# MCU.net
KiCad netlist of a schematic drawn in Altium Designer
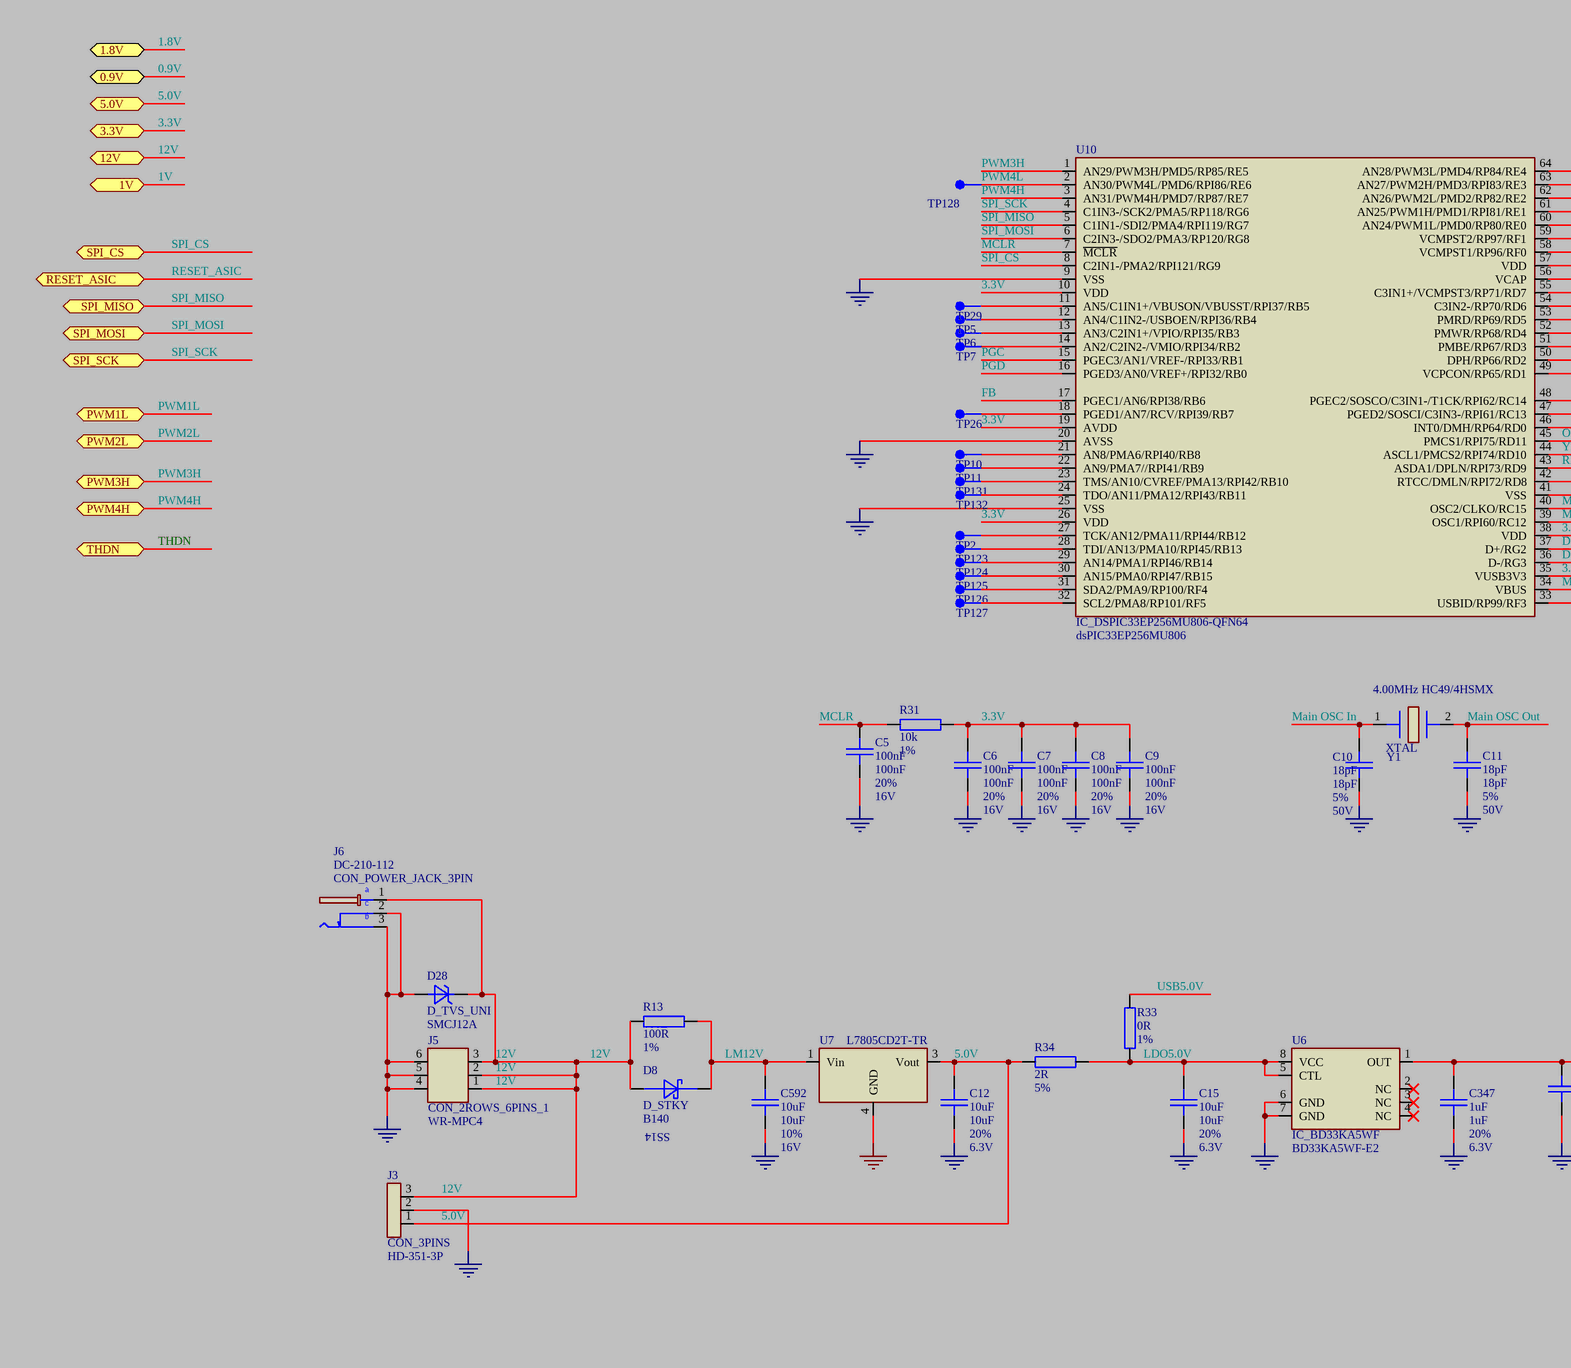
[diagram p0: MCU.SchDoc, left]
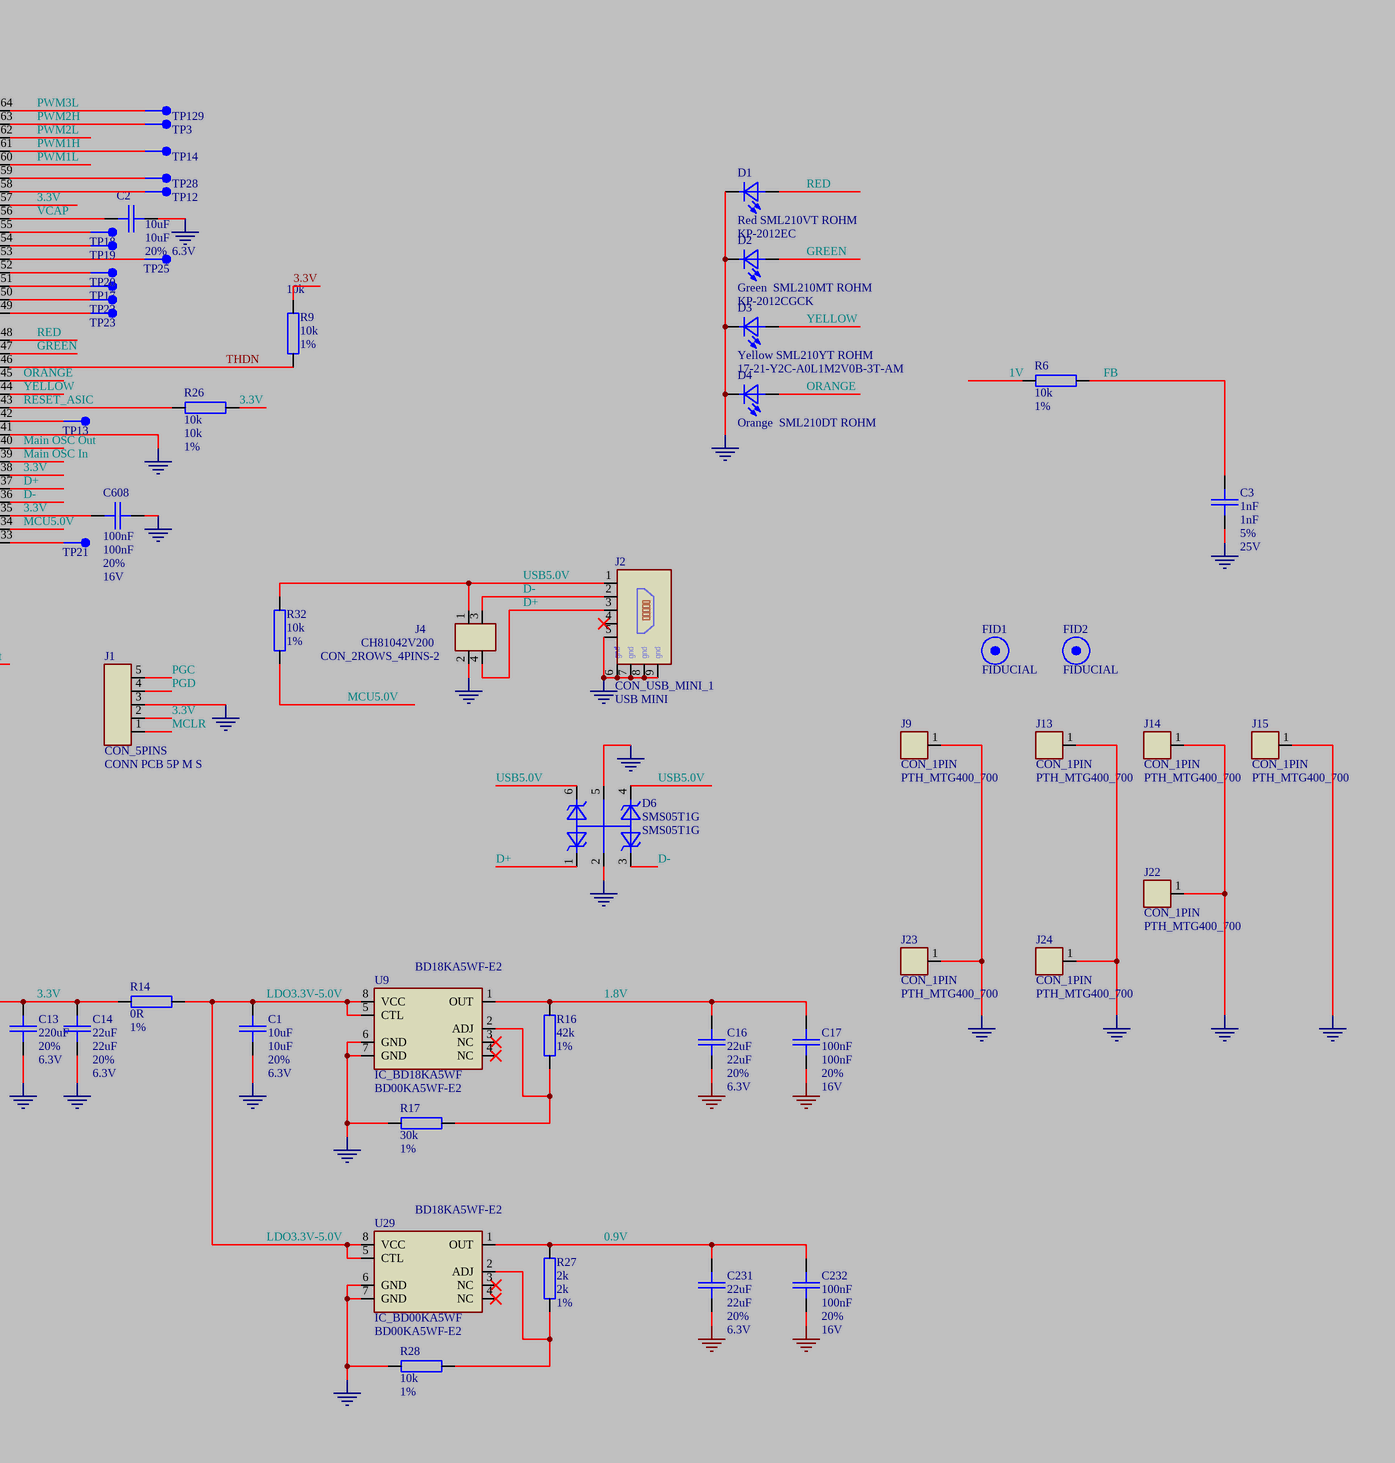
[diagram p1: MCU.SchDoc, right]

(export (version "E")
  (design (tool "Eeschema 10.0.6"))
  (components
    (comp (ref "C1")
      (value "10uF")
      (footprint "SMD_0603_CAPC1608X95N")
      (fields
        (field (name "DB_PART_NUMBER") "CAP000043646")
        (field (name "DB_VALUE") "10uF")
        (field (name "DB_TOLERANCE") "20%")
        (field (name "DB_VOLTAGE") "6.3V")
        (field (name "DB_MANUFACTURER_PART") "KEMET    C0603C106M9PAC")
        (field (name "DB_APPROVED_BY") "ISHIDDEN=T")
      )
      (libsource (lib "Database_Libs1") (part "C"))
    )
    (comp (ref "C2")
      (value "10uF")
      (footprint "SMD_0603_CAPC1608X95N")
      (fields
        (field (name "DB_PART_NUMBER") "CAP000043646")
        (field (name "DB_VALUE") "10uF")
        (field (name "DB_TOLERANCE") "20%")
        (field (name "DB_VOLTAGE") "6.3V")
        (field (name "DB_MANUFACTURER_PART") "KEMET    C0603C106M9PAC")
        (field (name "DB_APPROVED_BY") "ISHIDDEN=T")
      )
      (libsource (lib "Database_Libs1") (part "C"))
    )
    (comp (ref "C3")
      (value "1nF")
      (footprint "SMD_0603_CAPC1608X95N")
      (fields
        (field (name "DB_PART_NUMBER") "CAP000024113")
        (field (name "DB_VALUE") "1nF")
        (field (name "DB_TOLERANCE") "5%")
        (field (name "DB_VOLTAGE") "25V")
        (field (name "DB_MANUFACTURER_PART") "KEMET    C0603C102J3RAC")
        (field (name "DB_APPROVED_BY") "ISHIDDEN=T")
      )
      (libsource (lib "Database_Libs1") (part "C"))
    )
    (comp (ref "C5")
      (value "100nF")
      (footprint "SMD_0603_CAPC1608X95N")
      (fields
        (field (name "DB_PART_NUMBER") "CAP000027236")
        (field (name "DB_VALUE") "100nF")
        (field (name "DB_TOLERANCE") "20%")
        (field (name "DB_VOLTAGE") "16V")
        (field (name "DB_MANUFACTURER_PART") "KEMET    C0603C104M4RAC")
        (field (name "DB_APPROVED_BY") "ISHIDDEN=T")
      )
      (libsource (lib "Database_Libs1") (part "C"))
    )
    (comp (ref "C6")
      (value "100nF")
      (footprint "SMD_0603_CAPC1608X95N")
      (fields
        (field (name "DB_PART_NUMBER") "CAP000027236")
        (field (name "DB_VALUE") "100nF")
        (field (name "DB_TOLERANCE") "20%")
        (field (name "DB_VOLTAGE") "16V")
        (field (name "DB_MANUFACTURER_PART") "KEMET    C0603C104M4RAC")
        (field (name "DB_APPROVED_BY") "ISHIDDEN=T")
      )
      (libsource (lib "Database_Libs1") (part "C"))
    )
    (comp (ref "C7")
      (value "100nF")
      (footprint "SMD_0603_CAPC1608X95N")
      (fields
        (field (name "DB_PART_NUMBER") "CAP000027236")
        (field (name "DB_VALUE") "100nF")
        (field (name "DB_TOLERANCE") "20%")
        (field (name "DB_VOLTAGE") "16V")
        (field (name "DB_MANUFACTURER_PART") "KEMET    C0603C104M4RAC")
        (field (name "DB_APPROVED_BY") "ISHIDDEN=T")
      )
      (libsource (lib "Database_Libs1") (part "C"))
    )
    (comp (ref "C8")
      (value "100nF")
      (footprint "SMD_0603_CAPC1608X95N")
      (fields
        (field (name "DB_PART_NUMBER") "CAP000027236")
        (field (name "DB_VALUE") "100nF")
        (field (name "DB_TOLERANCE") "20%")
        (field (name "DB_VOLTAGE") "16V")
        (field (name "DB_MANUFACTURER_PART") "KEMET    C0603C104M4RAC")
        (field (name "DB_APPROVED_BY") "ISHIDDEN=T")
      )
      (libsource (lib "Database_Libs1") (part "C"))
    )
    (comp (ref "C9")
      (value "100nF")
      (footprint "SMD_0603_CAPC1608X95N")
      (fields
        (field (name "DB_PART_NUMBER") "CAP000027236")
        (field (name "DB_VALUE") "100nF")
        (field (name "DB_TOLERANCE") "20%")
        (field (name "DB_VOLTAGE") "16V")
        (field (name "DB_MANUFACTURER_PART") "KEMET    C0603C104M4RAC")
        (field (name "DB_APPROVED_BY") "ISHIDDEN=T")
      )
      (libsource (lib "Database_Libs1") (part "C"))
    )
    (comp (ref "C10")
      (value "18pF")
      (footprint "SMD_0603_CAPC1608X95N")
      (fields
        (field (name "DB_PART_NUMBER") "CAP000031922")
        (field (name "DB_VALUE") "18pF")
        (field (name "DB_TOLERANCE") "5%")
        (field (name "DB_VOLTAGE") "50V")
        (field (name "DB_MANUFACTURER_PART") "KEMET    C0603C180J5GAC")
        (field (name "DB_APPROVED_BY") "ISHIDDEN=T")
      )
      (libsource (lib "Database_Libs1") (part "C"))
    )
    (comp (ref "C11")
      (value "18pF")
      (footprint "SMD_0603_CAPC1608X95N")
      (fields
        (field (name "DB_PART_NUMBER") "CAP000031922")
        (field (name "DB_VALUE") "18pF")
        (field (name "DB_TOLERANCE") "5%")
        (field (name "DB_VOLTAGE") "50V")
        (field (name "DB_MANUFACTURER_PART") "KEMET    C0603C180J5GAC")
        (field (name "DB_APPROVED_BY") "ISHIDDEN=T")
      )
      (libsource (lib "Database_Libs1") (part "C"))
    )
    (comp (ref "C12")
      (value "10uF")
      (footprint "SMD_0603_CAPC1608X95N")
      (fields
        (field (name "DB_PART_NUMBER") "CAP000043646")
        (field (name "DB_VALUE") "10uF")
        (field (name "DB_TOLERANCE") "20%")
        (field (name "DB_VOLTAGE") "6.3V")
        (field (name "DB_MANUFACTURER_PART") "KEMET    C0603C106M9PAC")
        (field (name "DB_APPROVED_BY") "ISHIDDEN=T")
      )
      (libsource (lib "Database_Libs1") (part "C"))
    )
    (comp (ref "C13")
      (value "220uF")
      (footprint "SMD_1210_CAPC3225X279N")
      (fields
        (field (name "DB_PART_NUMBER") "CAP000047355")
        (field (name "DB_VALUE") "220uF")
        (field (name "DB_TOLERANCE") "20%")
        (field (name "DB_VOLTAGE") "6.3V")
        (field (name "DB_MANUFACTURER_PART") "SAMSUNG    CL32A227MQVNNNE")
        (field (name "DB_APPROVED_BY") "VSN")
      )
      (libsource (lib "Database_Libs1") (part "C"))
    )
    (comp (ref "C14")
      (value "22uF")
      (footprint "SMD_0805_CAPC2012X145N")
      (fields
        (field (name "DB_PART_NUMBER") "CAP000043686")
        (field (name "DB_VALUE") "22uF")
        (field (name "DB_TOLERANCE") "20%")
        (field (name "DB_VOLTAGE") "6.3V")
        (field (name "DB_MANUFACTURER_PART") "KEMET    C0805C226M9PAC")
        (field (name "DB_APPROVED_BY") "ISHIDDEN=T")
      )
      (libsource (lib "Database_Libs1") (part "C"))
    )
    (comp (ref "C15")
      (value "10uF")
      (footprint "SMD_0603_CAPC1608X95N")
      (fields
        (field (name "DB_PART_NUMBER") "CAP000043646")
        (field (name "DB_VALUE") "10uF")
        (field (name "DB_TOLERANCE") "20%")
        (field (name "DB_VOLTAGE") "6.3V")
        (field (name "DB_MANUFACTURER_PART") "KEMET    C0603C106M9PAC")
        (field (name "DB_APPROVED_BY") "ISHIDDEN=T")
      )
      (libsource (lib "Database_Libs1") (part "C"))
    )
    (comp (ref "C16")
      (value "22uF")
      (footprint "SMD_0805_CAPC2012X145N")
      (fields
        (field (name "DB_PART_NUMBER") "CAP000043686")
        (field (name "DB_VALUE") "22uF")
        (field (name "DB_TOLERANCE") "20%")
        (field (name "DB_VOLTAGE") "6.3V")
        (field (name "DB_MANUFACTURER_PART") "KEMET    C0805C226M9PAC")
        (field (name "DB_APPROVED_BY") "ISHIDDEN=T")
      )
      (libsource (lib "Database_Libs1") (part "C"))
    )
    (comp (ref "C17")
      (value "100nF")
      (footprint "SMD_0603_CAPC1608X95N")
      (fields
        (field (name "DB_PART_NUMBER") "CAP000027236")
        (field (name "DB_VALUE") "100nF")
        (field (name "DB_TOLERANCE") "20%")
        (field (name "DB_VOLTAGE") "16V")
        (field (name "DB_MANUFACTURER_PART") "KEMET    C0603C104M4RAC")
        (field (name "DB_APPROVED_BY") "ISHIDDEN=T")
      )
      (libsource (lib "Database_Libs1") (part "C"))
    )
    (comp (ref "C231")
      (value "22uF")
      (footprint "SMD_0805_CAPC2012X145N")
      (fields
        (field (name "DB_PART_NUMBER") "CAP000043686")
        (field (name "DB_VALUE") "22uF")
        (field (name "DB_TOLERANCE") "20%")
        (field (name "DB_VOLTAGE") "6.3V")
        (field (name "DB_MANUFACTURER_PART") "KEMET    C0805C226M9PAC")
        (field (name "DB_APPROVED_BY") "ISHIDDEN=T")
      )
      (libsource (lib "Database_Libs1") (part "C"))
    )
    (comp (ref "C232")
      (value "100nF")
      (footprint "SMD_0603_CAPC1608X95N")
      (fields
        (field (name "DB_PART_NUMBER") "CAP000027236")
        (field (name "DB_VALUE") "100nF")
        (field (name "DB_TOLERANCE") "20%")
        (field (name "DB_VOLTAGE") "16V")
        (field (name "DB_MANUFACTURER_PART") "KEMET    C0603C104M4RAC")
        (field (name "DB_APPROVED_BY") "ISHIDDEN=T")
      )
      (libsource (lib "Database_Libs1") (part "C"))
    )
    (comp (ref "C347")
      (value "1uF")
      (footprint "SMD_0603_CAPC1608X95N")
      (fields
        (field (name "DB_PART_NUMBER") "CAP000043344")
        (field (name "DB_VALUE") "1uF")
        (field (name "DB_TOLERANCE") "20%")
        (field (name "DB_VOLTAGE") "6.3V")
        (field (name "DB_MANUFACTURER_PART") "KEMET    C0603C105M9PAC")
        (field (name "DB_APPROVED_BY") "ISHIDDEN=T")
      )
      (libsource (lib "Database_Libs1") (part "C"))
    )
    (comp (ref "C592")
      (value "10uF")
      (footprint "SMD_0805_CAPC2012X145N")
      (fields
        (field (name "DB_PART_NUMBER") "CAP000043636")
        (field (name "DB_VALUE") "10uF")
        (field (name "DB_TOLERANCE") "10%")
        (field (name "DB_VOLTAGE") "16V")
        (field (name "DB_MANUFACTURER_PART") "KEMET    C0805C106K4PAC")
        (field (name "DB_APPROVED_BY") "ISHIDDEN=T")
      )
      (libsource (lib "Database_Libs1") (part "C"))
    )
    (comp (ref "C608")
      (value "100nF")
      (footprint "SMD_0603_CAPC1608X95N")
      (fields
        (field (name "DB_PART_NUMBER") "CAP000027236")
        (field (name "DB_VALUE") "100nF")
        (field (name "DB_TOLERANCE") "20%")
        (field (name "DB_VOLTAGE") "16V")
        (field (name "DB_MANUFACTURER_PART") "KEMET    C0603C104M4RAC")
        (field (name "DB_APPROVED_BY") "ISHIDDEN=T")
      )
      (libsource (lib "Database_Libs1") (part "C"))
    )
    (comp (ref "D1")
      (value "Red SML210VT ROHM")
      (footprint "SMD_0805_LED2012X100N")
      (fields
        (field (name "DB_PART_NUMBER") "OPT000000095")
        (field (name "DB_MANUFACTURER_PART") "KINGBRIGHT       KP-2012EC")
        (field (name "DB_VALUE") "KP-2012EC")
        (field (name "DB_APPROVED_BY") "VSN")
      )
      (libsource (lib "Database_Libs1") (part "LED"))
    )
    (comp (ref "D2")
      (value "Green  SML210MT ROHM")
      (footprint "SMD_0805_LED2012X100N")
      (fields
        (field (name "DB_PART_NUMBER") "OPT000000096")
        (field (name "DB_MANUFACTURER_PART") "KINGBRIGHT       KP-2012CGCK")
        (field (name "DB_VALUE") "KP-2012CGCK")
        (field (name "DB_APPROVED_BY") "VSN")
      )
      (libsource (lib "Database_Libs1") (part "LED"))
    )
    (comp (ref "D3")
      (value "Yellow SML210YT ROHM")
      (footprint "SMD_0805_LED2012X100N")
      (fields
        (field (name "DB_PART_NUMBER") "OPT000000092")
        (field (name "DB_MANUFACTURER_PART") "EVERLIGHT       17-21-Y2C-A0L1M2V0B-3T-AM")
        (field (name "DB_VALUE") "17-21-Y2C-A0L1M2V0B-3T-AM")
        (field (name "DB_APPROVED_BY") "VSN")
      )
      (libsource (lib "Database_Libs1") (part "LED"))
    )
    (comp (ref "D4")
      (value "Orange  SML210DT ROHM")
      (footprint "SMD_0805_LED2012X100N")
      (fields
        (field (name "DB_PART_NUMBER") "OPT000000096")
        (field (name "DB_MANUFACTURER_PART") "KINGBRIGHT       KP-2012CGCK")
        (field (name "DB_APPROVED_BY") "VSN")
      )
      (libsource (lib "altium-import") (part "root_0_LED_Orange_"))
    )
    (comp (ref "D6")
      (value "SMS05T1G")
      (footprint "SMD_SOT457_SOT95P275X110-6N")
      (fields
        (field (name "DB_PART_NUMBER") "DDE000002846")
        (field (name "DB_VALUE") "SMS05T1G")
        (field (name "DB_MANUFACTURER_PART") "ON SEMICONDUCTOR        SMS05T1G")
        (field (name "DB_APPROVED_BY") "VSN")
      )
      (libsource (lib "Database_Libs1") (part "D_TVS_QUAD_C1A2C3C4A5C6"))
    )
    (comp (ref "D8")
      (value "D_STKY")
      (footprint "SMD_DO214AC_SMA")
      (fields
        (field (name "DB_PART_NUMBER") "DDE000000580")
        (field (name "DB_VALUE") "B140")
        (field (name "DB_MANUFACTURER_PART") "Diodes        B140")
        (field (name "DB_APPROVED_BY") "ISHIDDEN=T")
      )
      (libsource (lib "Database_Libs1") (part "D_STKY"))
    )
    (comp (ref "D28")
      (value "D_TVS_UNI")
      (footprint "SMD_DO214AC_SMC")
      (fields
        (field (name "DB_PART_NUMBER") "DDE000001725")
        (field (name "DB_VALUE") "SMCJ12A")
        (field (name "DB_MANUFACTURER_PART") "Diodes        SMCJ12A")
        (field (name "DB_APPROVED_BY") "ISHIDDEN=T")
      )
      (libsource (lib "Database_Libs1") (part "D_TVS_UNI"))
    )
    (comp (ref "FID1")
      (value "FIDUCIAL")
      (footprint "FID100X200")
      (fields
        (field (name "DB_PART_NUMBER") "FID000000001")
        (field (name "DB_MANUFACTURER_PART") "ISHIDDEN=T")
        (field (name "DB_APPROVED_BY") "ISHIDDEN=T")
      )
      (libsource (lib "Database_Libs1") (part "FIDUCIAL"))
    )
    (comp (ref "FID2")
      (value "FIDUCIAL")
      (footprint "FID100X200")
      (fields
        (field (name "DB_PART_NUMBER") "FID000000001")
        (field (name "DB_MANUFACTURER_PART") "ISHIDDEN=T")
        (field (name "DB_APPROVED_BY") "ISHIDDEN=T")
      )
      (libsource (lib "Database_Libs1") (part "FIDUCIAL"))
    )
    (comp (ref "J1")
      (value "CON_5PINS")
      (footprint "PTH_HDRV05W64P254_1X05")
      (fields
        (field (name "DB_PART_NUMBER") "CON000000006")
        (field (name "DB_VALUE") "CONN PCB 5P M S")
        (field (name "DB_MANUFACTURER_PART") "W+P        143-12-005-00")
        (field (name "DB_APPROVED_BY") "VSN")
      )
      (libsource (lib "Database_Libs1") (part "CON_5PINS"))
    )
    (comp (ref "J2")
      (value "CON_USB_MINI_1")
      (footprint "SMD_CON-CVILUX-CU04-SCM15B0")
      (fields
        (field (name "DB_PART_NUMBER") "CON000000048")
        (field (name "DB_VALUE") "USB MINI")
        (field (name "DB_MANUFACTURER_PART") "CVILUX       CU04-SCM15B0-R0-LF")
        (field (name "DB_APPROVED_BY") "VSN")
      )
      (libsource (lib "Database_Libs1") (part "CON_USB_MINI_1"))
    )
    (comp (ref "J3")
      (value "CON_3PINS")
      (footprint "PTH_CON_HD-351-3P")
      (fields
        (field (name "DB_PART_NUMBER") "CON000000272")
        (field (name "DB_VALUE") "HD-351-3P")
        (field (name "DB_MANUFACTURER_PART") "HOW DER      HD-351-3P")
        (field (name "DB_APPROVED_BY") "VSN")
      )
      (libsource (lib "Database_Libs1") (part "CON_3PINS"))
    )
    (comp (ref "J4")
      (value "CON_2ROWS_4PINS-2")
      (footprint "PTH_HDRV40W6240P254_2X02_M")
      (fields
        (field (name "DB_PART_NUMBER") "CON000000298")
        (field (name "DB_VALUE") "CH81042V200")
        (field (name "DB_MANUFACTURER_PART") "CVILUX        CH81042V200")
        (field (name "DB_APPROVED_BY") "VSN")
      )
      (libsource (lib "Database_Libs1") (part "CON_2ROWS_4PINS-2"))
    )
    (comp (ref "J5")
      (value "CON_2ROWS_6PINS_1")
      (footprint "PTH_CON_WR-MRC4-6P")
      (fields
        (field (name "DB_PART_NUMBER") "CON000000271")
        (field (name "DB_VALUE") "WR-MPC4")
        (field (name "DB_MANUFACTURER_PART") "WE         649 006 295 22")
        (field (name "DB_APPROVED_BY") "VSN")
      )
      (libsource (lib "Database_Libs1") (part "CON_2ROWS_6PINS_1"))
    )
    (comp (ref "J6")
      (value "CON_POWER_JACK_3PIN")
      (footprint "PTH_DC-POWER-JACK_210-112")
      (fields
        (field (name "DB_PART_NUMBER") "CON000000026")
        (field (name "DB_VALUE") "DC-210-112")
        (field (name "DB_MANUFACTURER_PART") "HONBO       DC-210-112")
        (field (name "DB_APPROVED_BY") "VSN")
      )
      (libsource (lib "Database_Libs1") (part "CON_POWER_JACK_3PIN"))
    )
    (comp (ref "J9")
      (value "CON_1PIN")
      (footprint "PTH_MTG400_700")
      (fields
        (field (name "DB_PART_NUMBER") "MTH000000030")
        (field (name "DB_VALUE") "PTH_MTG400_700")
        (field (name "DB_APPROVED_BY") "VSN")
      )
      (libsource (lib "Database_Libs1") (part "CON_1PIN"))
    )
    (comp (ref "J13")
      (value "CON_1PIN")
      (footprint "PTH_MTG400_700")
      (fields
        (field (name "DB_PART_NUMBER") "MTH000000030")
        (field (name "DB_VALUE") "PTH_MTG400_700")
        (field (name "DB_APPROVED_BY") "VSN")
      )
      (libsource (lib "Database_Libs1") (part "CON_1PIN"))
    )
    (comp (ref "J14")
      (value "CON_1PIN")
      (footprint "PTH_MTG400_700")
      (fields
        (field (name "DB_PART_NUMBER") "MTH000000030")
        (field (name "DB_VALUE") "PTH_MTG400_700")
        (field (name "DB_APPROVED_BY") "VSN")
      )
      (libsource (lib "Database_Libs1") (part "CON_1PIN"))
    )
    (comp (ref "J15")
      (value "CON_1PIN")
      (footprint "PTH_MTG400_700")
      (fields
        (field (name "DB_PART_NUMBER") "MTH000000030")
        (field (name "DB_VALUE") "PTH_MTG400_700")
        (field (name "DB_APPROVED_BY") "VSN")
      )
      (libsource (lib "Database_Libs1") (part "CON_1PIN"))
    )
    (comp (ref "J22")
      (value "CON_1PIN")
      (footprint "PTH_MTG400_700")
      (fields
        (field (name "DB_PART_NUMBER") "MTH000000030")
        (field (name "DB_VALUE") "PTH_MTG400_700")
        (field (name "DB_APPROVED_BY") "VSN")
      )
      (libsource (lib "Database_Libs1") (part "CON_1PIN"))
    )
    (comp (ref "J23")
      (value "CON_1PIN")
      (footprint "PTH_MTG400_700")
      (fields
        (field (name "DB_PART_NUMBER") "MTH000000030")
        (field (name "DB_VALUE") "PTH_MTG400_700")
        (field (name "DB_APPROVED_BY") "VSN")
      )
      (libsource (lib "Database_Libs1") (part "CON_1PIN"))
    )
    (comp (ref "J24")
      (value "CON_1PIN")
      (footprint "PTH_MTG400_700")
      (fields
        (field (name "DB_PART_NUMBER") "MTH000000030")
        (field (name "DB_VALUE") "PTH_MTG400_700")
        (field (name "DB_APPROVED_BY") "VSN")
      )
      (libsource (lib "Database_Libs1") (part "CON_1PIN"))
    )
    (comp (ref "R6")
      (value "10k")
      (footprint "SMD_0603_RESC1608X55N")
      (fields
        (field (name "DB_PART_NUMBER") "RES000008663")
        (field (name "DB_VALUE") "10k")
        (field (name "DB_TOLERANCE") "1%")
        (field (name "DB_MANUFACTURER_PART") "YAGEO    RC0603FR-0710KL")
        (field (name "DB_APPROVED_BY") "VSN")
      )
      (libsource (lib "Database_Libs1") (part "R"))
    )
    (comp (ref "R9")
      (value "10k")
      (footprint "SMD_0603_RESC1608X55N")
      (fields
        (field (name "DB_PART_NUMBER") "RES000008663")
        (field (name "DB_VALUE") "10k")
        (field (name "DB_TOLERANCE") "1%")
        (field (name "DB_MANUFACTURER_PART") "YAGEO    RC0603FR-0710KL")
        (field (name "DB_APPROVED_BY") "VSN")
      )
      (libsource (lib "Database_Libs1") (part "R"))
    )
    (comp (ref "R13")
      (value "100R")
      (footprint "SMD_1206_RESC3216X65N")
      (fields
        (field (name "DB_PART_NUMBER") "RES000006922")
        (field (name "DB_VALUE") "100R")
        (field (name "DB_TOLERANCE") "1%")
        (field (name "DB_MANUFACTURER_PART") "YAGEO    RC1206FR-07100R")
        (field (name "DB_APPROVED_BY") "ISHIDDEN=T")
      )
      (libsource (lib "Database_Libs1") (part "R"))
    )
    (comp (ref "R14")
      (value "0R")
      (footprint "SMD_1206_RESC3216X65N")
      (fields
        (field (name "DB_PART_NUMBER") "RES000008756")
        (field (name "DB_VALUE") "0R")
        (field (name "DB_TOLERANCE") "1%")
        (field (name "DB_MANUFACTURER_PART") "YAGEO    AC1206FR-070RL")
        (field (name "DB_APPROVED_BY") "VSN")
      )
      (libsource (lib "Database_Libs1") (part "R"))
    )
    (comp (ref "R16")
      (value "R_42k")
      (footprint "SMD_0603_RESC1608X55N")
      (fields
        (field (name "DB_PART_NUMBER") "RES000001590")
        (field (name "DB_VALUE") "42k")
        (field (name "DB_TOLERANCE") "1%")
        (field (name "DB_MANUFACTURER_PART") "YAGEO    RC0603FR-0741K2")
        (field (name "DB_APPROVED_BY") "ISHIDDEN=T")
      )
      (libsource (lib "Schlib1") (part "R_42k"))
    )
    (comp (ref "R17")
      (value "30k")
      (footprint "SMD_0603_RESC1608X55N")
      (fields
        (field (name "DB_PART_NUMBER") "RES000006287")
        (field (name "DB_VALUE") "30k")
        (field (name "DB_TOLERANCE") "1%")
        (field (name "DB_MANUFACTURER_PART") "YAGEO    RC0603FR-0730K")
        (field (name "DB_APPROVED_BY") "ISHIDDEN=T")
      )
      (libsource (lib "Database_Libs1") (part "R"))
    )
    (comp (ref "R26")
      (value "10k")
      (footprint "SMD_0603_RESC1608X55N")
      (fields
        (field (name "DB_PART_NUMBER") "RES000008663")
        (field (name "DB_VALUE") "10k")
        (field (name "DB_TOLERANCE") "1%")
        (field (name "DB_MANUFACTURER_PART") "YAGEO    RC0603FR-0710KL")
        (field (name "DB_APPROVED_BY") "VSN")
      )
      (libsource (lib "Database_Libs1") (part "R"))
    )
    (comp (ref "R27")
      (value "2k")
      (footprint "SMD_0603_RESC1608X55N")
      (fields
        (field (name "DB_PART_NUMBER") "RES000008586")
        (field (name "DB_VALUE") "2k")
        (field (name "DB_TOLERANCE") "1%")
        (field (name "DB_MANUFACTURER_PART") "YAGEO       AC0603FR-072KL")
        (field (name "DB_APPROVED_BY") "VSN")
      )
      (libsource (lib "Database_Libs1") (part "R"))
    )
    (comp (ref "R28")
      (value "10k")
      (footprint "SMD_0603_RESC1608X55N")
      (fields
        (field (name "DB_PART_NUMBER") "RES000008663")
        (field (name "DB_VALUE") "10k")
        (field (name "DB_TOLERANCE") "1%")
        (field (name "DB_MANUFACTURER_PART") "YAGEO    RC0603FR-0710KL")
        (field (name "DB_APPROVED_BY") "VSN")
      )
      (libsource (lib "Database_Libs1") (part "R"))
    )
    (comp (ref "R31")
      (value "10k")
      (footprint "SMD_0603_RESC1608X55N")
      (fields
        (field (name "DB_PART_NUMBER") "RES000008663")
        (field (name "DB_VALUE") "10k")
        (field (name "DB_TOLERANCE") "1%")
        (field (name "DB_MANUFACTURER_PART") "YAGEO    RC0603FR-0710KL")
        (field (name "DB_APPROVED_BY") "VSN")
      )
      (libsource (lib "Database_Libs1") (part "R"))
    )
    (comp (ref "R32")
      (value "10k")
      (footprint "SMD_0603_RESC1608X55N")
      (fields
        (field (name "DB_PART_NUMBER") "RES000008663")
        (field (name "DB_VALUE") "10k")
        (field (name "DB_TOLERANCE") "1%")
        (field (name "DB_MANUFACTURER_PART") "YAGEO    RC0603FR-0710KL")
        (field (name "DB_APPROVED_BY") "VSN")
      )
      (libsource (lib "Database_Libs1") (part "R"))
    )
    (comp (ref "R33")
      (value "0R")
      (footprint "SMD_0603_RESC1608X55N")
      (fields
        (field (name "DB_PART_NUMBER") "RES000008926")
        (field (name "DB_VALUE") "0R")
        (field (name "DB_TOLERANCE") "1%")
        (field (name "DB_MANUFACTURER_PART") "YAGEO    AC0603FR-070RL")
        (field (name "DB_APPROVED_BY") "VSN")
      )
      (libsource (lib "Database_Libs1") (part "R"))
    )
    (comp (ref "R34")
      (value "2R")
      (footprint "SMD_1206_RESC3216X65N")
      (fields
        (field (name "DB_PART_NUMBER") "RES000007051")
        (field (name "DB_VALUE") "2R")
        (field (name "DB_TOLERANCE") "5%")
        (field (name "DB_MANUFACTURER_PART") "YAGEO    RC1206JR-072R")
        (field (name "DB_APPROVED_BY") "ISHIDDEN=T")
      )
      (libsource (lib "Database_Libs1") (part "R"))
    )
    (comp (ref "TP2")
      (value "TEST_POINT_1")
      (footprint "SMD_TP_100-254")
      (fields
        (field (name "DB_PART_NUMBER") "TPO000000001")
        (field (name "DB_MANUFACTURER_PART") "ISHIDDEN=T")
        (field (name "DB_APPROVED_BY") "ISHIDDEN=T")
      )
      (libsource (lib "Database_Libs1") (part "TEST_POINT_1"))
    )
    (comp (ref "TP3")
      (value "TEST_POINT_1")
      (footprint "SMD_TP_100-254")
      (fields
        (field (name "DB_PART_NUMBER") "TPO000000001")
        (field (name "DB_MANUFACTURER_PART") "ISHIDDEN=T")
        (field (name "DB_APPROVED_BY") "ISHIDDEN=T")
      )
      (libsource (lib "Database_Libs1") (part "TEST_POINT_1"))
    )
    (comp (ref "TP5")
      (value "TEST_POINT_1")
      (footprint "SMD_TP_100-254")
      (fields
        (field (name "DB_PART_NUMBER") "TPO000000001")
        (field (name "DB_MANUFACTURER_PART") "ISHIDDEN=T")
        (field (name "DB_APPROVED_BY") "ISHIDDEN=T")
      )
      (libsource (lib "Database_Libs1") (part "TEST_POINT_1"))
    )
    (comp (ref "TP6")
      (value "TEST_POINT_1")
      (footprint "SMD_TP_100-254")
      (fields
        (field (name "DB_PART_NUMBER") "TPO000000001")
        (field (name "DB_MANUFACTURER_PART") "ISHIDDEN=T")
        (field (name "DB_APPROVED_BY") "ISHIDDEN=T")
      )
      (libsource (lib "Database_Libs1") (part "TEST_POINT_1"))
    )
    (comp (ref "TP7")
      (value "TEST_POINT_1")
      (footprint "SMD_TP_100-254")
      (fields
        (field (name "DB_PART_NUMBER") "TPO000000001")
        (field (name "DB_MANUFACTURER_PART") "ISHIDDEN=T")
        (field (name "DB_APPROVED_BY") "ISHIDDEN=T")
      )
      (libsource (lib "Database_Libs1") (part "TEST_POINT_1"))
    )
    (comp (ref "TP10")
      (value "TEST_POINT_1")
      (footprint "SMD_TP_100-254")
      (fields
        (field (name "DB_PART_NUMBER") "TPO000000001")
        (field (name "DB_MANUFACTURER_PART") "ISHIDDEN=T")
        (field (name "DB_APPROVED_BY") "ISHIDDEN=T")
      )
      (libsource (lib "Database_Libs1") (part "TEST_POINT_1"))
    )
    (comp (ref "TP11")
      (value "TEST_POINT_1")
      (footprint "SMD_TP_100-254")
      (fields
        (field (name "DB_PART_NUMBER") "TPO000000001")
        (field (name "DB_MANUFACTURER_PART") "ISHIDDEN=T")
        (field (name "DB_APPROVED_BY") "ISHIDDEN=T")
      )
      (libsource (lib "Database_Libs1") (part "TEST_POINT_1"))
    )
    (comp (ref "TP12")
      (value "TEST_POINT_1")
      (footprint "SMD_TP_100-254")
      (fields
        (field (name "DB_PART_NUMBER") "TPO000000001")
        (field (name "DB_MANUFACTURER_PART") "ISHIDDEN=T")
        (field (name "DB_APPROVED_BY") "ISHIDDEN=T")
      )
      (libsource (lib "Database_Libs1") (part "TEST_POINT_1"))
    )
    (comp (ref "TP13")
      (value "TEST_POINT_1")
      (footprint "SMD_TP_100-254")
      (fields
        (field (name "DB_PART_NUMBER") "TPO000000001")
        (field (name "DB_MANUFACTURER_PART") "ISHIDDEN=T")
        (field (name "DB_APPROVED_BY") "ISHIDDEN=T")
      )
      (libsource (lib "Database_Libs1") (part "TEST_POINT_1"))
    )
    (comp (ref "TP14")
      (value "TEST_POINT_1")
      (footprint "SMD_TP_100-254")
      (fields
        (field (name "DB_PART_NUMBER") "TPO000000001")
        (field (name "DB_MANUFACTURER_PART") "ISHIDDEN=T")
        (field (name "DB_APPROVED_BY") "ISHIDDEN=T")
      )
      (libsource (lib "Database_Libs1") (part "TEST_POINT_1"))
    )
    (comp (ref "TP17")
      (value "TEST_POINT_1")
      (footprint "SMD_TP_100-254")
      (fields
        (field (name "DB_PART_NUMBER") "TPO000000001")
        (field (name "DB_MANUFACTURER_PART") "ISHIDDEN=T")
        (field (name "DB_APPROVED_BY") "ISHIDDEN=T")
      )
      (libsource (lib "Database_Libs1") (part "TEST_POINT_1"))
    )
    (comp (ref "TP18")
      (value "TEST_POINT_1")
      (footprint "SMD_TP_100-254")
      (fields
        (field (name "DB_PART_NUMBER") "TPO000000001")
        (field (name "DB_MANUFACTURER_PART") "ISHIDDEN=T")
        (field (name "DB_APPROVED_BY") "ISHIDDEN=T")
      )
      (libsource (lib "Database_Libs1") (part "TEST_POINT_1"))
    )
    (comp (ref "TP19")
      (value "TEST_POINT_1")
      (footprint "SMD_TP_100-254")
      (fields
        (field (name "DB_PART_NUMBER") "TPO000000001")
        (field (name "DB_MANUFACTURER_PART") "ISHIDDEN=T")
        (field (name "DB_APPROVED_BY") "ISHIDDEN=T")
      )
      (libsource (lib "Database_Libs1") (part "TEST_POINT_1"))
    )
    (comp (ref "TP20")
      (value "TEST_POINT_1")
      (footprint "SMD_TP_100-254")
      (fields
        (field (name "DB_PART_NUMBER") "TPO000000001")
        (field (name "DB_MANUFACTURER_PART") "ISHIDDEN=T")
        (field (name "DB_APPROVED_BY") "ISHIDDEN=T")
      )
      (libsource (lib "Database_Libs1") (part "TEST_POINT_1"))
    )
    (comp (ref "TP21")
      (value "TEST_POINT_1")
      (footprint "SMD_TP_100-254")
      (fields
        (field (name "DB_PART_NUMBER") "TPO000000001")
        (field (name "DB_MANUFACTURER_PART") "ISHIDDEN=T")
        (field (name "DB_APPROVED_BY") "ISHIDDEN=T")
      )
      (libsource (lib "Database_Libs1") (part "TEST_POINT_1"))
    )
    (comp (ref "TP22")
      (value "TEST_POINT_1")
      (footprint "SMD_TP_100-254")
      (fields
        (field (name "DB_PART_NUMBER") "TPO000000001")
        (field (name "DB_MANUFACTURER_PART") "ISHIDDEN=T")
        (field (name "DB_APPROVED_BY") "ISHIDDEN=T")
      )
      (libsource (lib "Database_Libs1") (part "TEST_POINT_1"))
    )
    (comp (ref "TP23")
      (value "TEST_POINT_1")
      (footprint "SMD_TP_100-254")
      (fields
        (field (name "DB_PART_NUMBER") "TPO000000001")
        (field (name "DB_MANUFACTURER_PART") "ISHIDDEN=T")
        (field (name "DB_APPROVED_BY") "ISHIDDEN=T")
      )
      (libsource (lib "Database_Libs1") (part "TEST_POINT_1"))
    )
    (comp (ref "TP25")
      (value "TEST_POINT_1")
      (footprint "SMD_TP_100-254")
      (fields
        (field (name "DB_PART_NUMBER") "TPO000000001")
        (field (name "DB_MANUFACTURER_PART") "ISHIDDEN=T")
        (field (name "DB_APPROVED_BY") "ISHIDDEN=T")
      )
      (libsource (lib "Database_Libs1") (part "TEST_POINT_1"))
    )
    (comp (ref "TP26")
      (value "TEST_POINT_1")
      (footprint "SMD_TP_100-254")
      (fields
        (field (name "DB_PART_NUMBER") "TPO000000001")
        (field (name "DB_MANUFACTURER_PART") "ISHIDDEN=T")
        (field (name "DB_APPROVED_BY") "ISHIDDEN=T")
      )
      (libsource (lib "Database_Libs1") (part "TEST_POINT_1"))
    )
    (comp (ref "TP28")
      (value "TEST_POINT_1")
      (footprint "SMD_TP_100-254")
      (fields
        (field (name "DB_PART_NUMBER") "TPO000000001")
        (field (name "DB_MANUFACTURER_PART") "ISHIDDEN=T")
        (field (name "DB_APPROVED_BY") "ISHIDDEN=T")
      )
      (libsource (lib "Database_Libs1") (part "TEST_POINT_1"))
    )
    (comp (ref "TP29")
      (value "TEST_POINT_1")
      (footprint "SMD_TP_100-254")
      (fields
        (field (name "DB_PART_NUMBER") "TPO000000001")
        (field (name "DB_MANUFACTURER_PART") "ISHIDDEN=T")
        (field (name "DB_APPROVED_BY") "ISHIDDEN=T")
      )
      (libsource (lib "Database_Libs1") (part "TEST_POINT_1"))
    )
    (comp (ref "TP123")
      (value "TEST_POINT_1")
      (footprint "SMD_TP_100-254")
      (fields
        (field (name "DB_PART_NUMBER") "TPO000000001")
        (field (name "DB_MANUFACTURER_PART") "ISHIDDEN=T")
        (field (name "DB_APPROVED_BY") "ISHIDDEN=T")
      )
      (libsource (lib "Database_Libs1") (part "TEST_POINT_1"))
    )
    (comp (ref "TP124")
      (value "TEST_POINT_1")
      (footprint "SMD_TP_100-254")
      (fields
        (field (name "DB_PART_NUMBER") "TPO000000001")
        (field (name "DB_MANUFACTURER_PART") "ISHIDDEN=T")
        (field (name "DB_APPROVED_BY") "ISHIDDEN=T")
      )
      (libsource (lib "Database_Libs1") (part "TEST_POINT_1"))
    )
    (comp (ref "TP125")
      (value "TEST_POINT_1")
      (footprint "SMD_TP_100-254")
      (fields
        (field (name "DB_PART_NUMBER") "TPO000000001")
        (field (name "DB_MANUFACTURER_PART") "ISHIDDEN=T")
        (field (name "DB_APPROVED_BY") "ISHIDDEN=T")
      )
      (libsource (lib "Database_Libs1") (part "TEST_POINT_1"))
    )
    (comp (ref "TP126")
      (value "TEST_POINT_1")
      (footprint "SMD_TP_100-254")
      (fields
        (field (name "DB_PART_NUMBER") "TPO000000001")
        (field (name "DB_MANUFACTURER_PART") "ISHIDDEN=T")
        (field (name "DB_APPROVED_BY") "ISHIDDEN=T")
      )
      (libsource (lib "Database_Libs1") (part "TEST_POINT_1"))
    )
    (comp (ref "TP127")
      (value "TEST_POINT_1")
      (footprint "SMD_TP_100-254")
      (fields
        (field (name "DB_PART_NUMBER") "TPO000000001")
        (field (name "DB_MANUFACTURER_PART") "ISHIDDEN=T")
        (field (name "DB_APPROVED_BY") "ISHIDDEN=T")
      )
      (libsource (lib "Database_Libs1") (part "TEST_POINT_1"))
    )
    (comp (ref "TP128")
      (value "TEST_POINT_1")
      (footprint "SMD_TP_100-254")
      (fields
        (field (name "DB_PART_NUMBER") "TPO000000001")
        (field (name "DB_MANUFACTURER_PART") "ISHIDDEN=T")
        (field (name "DB_APPROVED_BY") "ISHIDDEN=T")
      )
      (libsource (lib "Database_Libs1") (part "TEST_POINT_1"))
    )
    (comp (ref "TP129")
      (value "TEST_POINT_1")
      (footprint "SMD_TP_100-254")
      (fields
        (field (name "DB_PART_NUMBER") "TPO000000001")
        (field (name "DB_MANUFACTURER_PART") "ISHIDDEN=T")
        (field (name "DB_APPROVED_BY") "ISHIDDEN=T")
      )
      (libsource (lib "Database_Libs1") (part "TEST_POINT_1"))
    )
    (comp (ref "TP131")
      (value "TEST_POINT_1")
      (footprint "SMD_TP_100-254")
      (fields
        (field (name "DB_PART_NUMBER") "TPO000000001")
        (field (name "DB_MANUFACTURER_PART") "ISHIDDEN=T")
        (field (name "DB_APPROVED_BY") "ISHIDDEN=T")
      )
      (libsource (lib "Database_Libs1") (part "TEST_POINT_1"))
    )
    (comp (ref "TP132")
      (value "TEST_POINT_1")
      (footprint "SMD_TP_100-254")
      (fields
        (field (name "DB_PART_NUMBER") "TPO000000001")
        (field (name "DB_MANUFACTURER_PART") "ISHIDDEN=T")
        (field (name "DB_APPROVED_BY") "ISHIDDEN=T")
      )
      (libsource (lib "Database_Libs1") (part "TEST_POINT_1"))
    )
    (comp (ref "U6")
      (value "IC_BD33KA5WF")
      (footprint "SMD_SOIC127P620X160-8N")
      (fields
        (field (name "DB_PART_NUMBER") "PSU000000127")
        (field (name "DB_VALUE") "BD33KA5WF-E2")
        (field (name "DB_MANUFACTURER_PART") "ROHM        BD33KA5WF-E2")
        (field (name "DB_APPROVED_BY") "VSN")
      )
      (libsource (lib "Database_Libs1") (part "IC_BDXXKA5WF"))
    )
    (comp (ref "U7")
      (value "L7805CD2T-TR")
      (footprint "SMD_TO254P1542X460-3_4N")
      (fields
        (field (name "DB_PART_NUMBER") "PSU000000129")
        (field (name "DB_VALUE") "L7805CD2T-TR")
        (field (name "DB_MANUFACTURER_PART") "ST       L7805CD2T-TR")
        (field (name "DB_APPROVED_BY") "VSN")
      )
      (libsource (lib "Database_Libs1") (part "IC_IN1OUT3GND4"))
    )
    (comp (ref "U9")
      (value "IC_BD18KA5WF")
      (footprint "SMD_SOIC127P620X160-8N")
      (fields
        (field (name "DB_PART_NUMBER") "PSU000000128")
        (field (name "DB_VALUE") "BD00KA5WF-E2")
        (field (name "DB_MANUFACTURER_PART") "ROHM        BD00KA5WF-E2")
        (field (name "DB_APPROVED_BY") "VSN")
      )
      (libsource (lib "Database_Libs1") (part "IC_BD00KA5WF"))
    )
    (comp (ref "U10")
      (value "IC_DSPIC33EP256MU806-QFN64")
      (footprint "SMD_QFP50P1200X1200X120-64N")
      (fields
        (field (name "DB_PART_NUMBER") "MCU000000070")
        (field (name "DB_VALUE") "dsPIC33EP256MU806")
        (field (name "DB_MANUFACTURER_PART") "MICROCHIP        DSPIC33EP256MU806-E/PT")
        (field (name "DB_APPROVED_BY") "VSN")
      )
      (libsource (lib "Database_Libs1") (part "IC_DSPIC33EP256MU806-QFN64"))
    )
    (comp (ref "U29")
      (value "IC_BD00KA5WF")
      (footprint "SMD_SOIC127P620X160-8N")
      (fields
        (field (name "DB_PART_NUMBER") "PSU000000128")
        (field (name "DB_VALUE") "BD00KA5WF-E2")
        (field (name "DB_MANUFACTURER_PART") "ROHM        BD00KA5WF-E2")
        (field (name "DB_APPROVED_BY") "VSN")
      )
      (libsource (lib "Database_Libs1") (part "IC_BD00KA5WF"))
    )
    (comp (ref "Y1")
      (value "XTAL")
      (footprint "SMD_HC49_XTAL1140X480X420N")
      (fields
        (field (name "DB_PART_NUMBER") "OSC000000012")
        (field (name "DB_VALUE") "4.00MHz HC49/4HSMX")
        (field (name "DB_MANUFACTURER_PART") "IQD       4.00MHz HC49/4HSMX")
        (field (name "DB_APPROVED_BY") "VSN")
      )
      (libsource (lib "Database_Libs1") (part "XTAL"))
    )
  )
  (nets
    (net (code "1") (name "/0.9V") (class "Default")
      (node (ref "C231") (pin "1") (pinfunction "1_1") (pintype "passive"))
      (node (ref "C232") (pin "1") (pinfunction "1_1") (pintype "passive"))
      (node (ref "R27") (pin "1") (pinfunction "1_1") (pintype "passive"))
      (node (ref "U29") (pin "1") (pinfunction "OUT_1") (pintype "passive"))
    )
    (net (code "2") (name "/1.8V") (class "Default")
      (node (ref "C16") (pin "1") (pinfunction "1_1") (pintype "passive"))
      (node (ref "C17") (pin "1") (pinfunction "1_1") (pintype "passive"))
      (node (ref "R16") (pin "1") (pinfunction "1_1") (pintype "passive"))
      (node (ref "U9") (pin "1") (pinfunction "OUT_1") (pintype "passive"))
    )
    (net (code "3") (name "/1V") (class "Default")
      (node (ref "R6") (pin "2") (pinfunction "2_2") (pintype "passive"))
    )
    (net (code "4") (name "/3.3V") (class "Default")
      (node (ref "C13") (pin "2") (pinfunction "2_2") (pintype "passive"))
      (node (ref "C14") (pin "1") (pinfunction "1_1") (pintype "passive"))
      (node (ref "C347") (pin "1") (pinfunction "1_1") (pintype "passive"))
      (node (ref "C6") (pin "1") (pinfunction "1_1") (pintype "passive"))
      (node (ref "C608") (pin "1") (pinfunction "1_1") (pintype "passive"))
      (node (ref "C7") (pin "1") (pinfunction "1_1") (pintype "passive"))
      (node (ref "C8") (pin "1") (pinfunction "1_1") (pintype "passive"))
      (node (ref "C9") (pin "1") (pinfunction "1_1") (pintype "passive"))
      (node (ref "J1") (pin "2") (pinfunction "2_2") (pintype "passive"))
      (node (ref "R14") (pin "2") (pinfunction "2_2") (pintype "passive"))
      (node (ref "R26") (pin "1") (pinfunction "1_1") (pintype "passive"))
      (node (ref "R31") (pin "2") (pinfunction "2_2") (pintype "passive"))
      (node (ref "R9") (pin "2") (pinfunction "2_2") (pintype "passive"))
      (node (ref "U10") (pin "10") (pinfunction "VDD_10") (pintype "passive"))
      (node (ref "U10") (pin "19") (pinfunction "AVDD_19") (pintype "passive"))
      (node (ref "U10") (pin "26") (pinfunction "VDD_26") (pintype "passive"))
      (node (ref "U10") (pin "35") (pinfunction "VUSB3V3_35") (pintype "passive"))
      (node (ref "U10") (pin "38") (pinfunction "VDD_38") (pintype "passive"))
      (node (ref "U10") (pin "57") (pinfunction "VDD_57") (pintype "passive"))
      (node (ref "U6") (pin "1") (pinfunction "OUT_1") (pintype "passive"))
    )
    (net (code "5") (name "/5.0V") (class "Default")
      (node (ref "C12") (pin "1") (pinfunction "1_1") (pintype "passive"))
      (node (ref "J3") (pin "1") (pinfunction "1_1") (pintype "passive"))
      (node (ref "R34") (pin "2") (pinfunction "2_2") (pintype "passive"))
      (node (ref "U7") (pin "3") (pinfunction "Vout_3") (pintype "passive"))
    )
    (net (code "6") (name "/12V") (class "Default")
      (node (ref "D28") (pin "1") (pinfunction "C_1") (pintype "passive"))
      (node (ref "D8") (pin "2") (pinfunction "A_2") (pintype "passive"))
      (node (ref "J3") (pin "3") (pinfunction "3_3") (pintype "passive"))
      (node (ref "J5") (pin "1") (pinfunction "1_1") (pintype "passive"))
      (node (ref "J5") (pin "2") (pinfunction "2_2") (pintype "passive"))
      (node (ref "J5") (pin "3") (pinfunction "3_3") (pintype "passive"))
      (node (ref "J6") (pin "1") (pinfunction "1_1") (pintype "passive"))
      (node (ref "R13") (pin "2") (pinfunction "2_2") (pintype "passive"))
    )
    (net (code "7") (name "/D+") (class "Default")
      (node (ref "D6") (pin "1") (pinfunction "1_1") (pintype "passive"))
      (node (ref "J2") (pin "3") (pinfunction "3_3") (pintype "passive"))
      (node (ref "J4") (pin "4") (pinfunction "4_4") (pintype "passive"))
      (node (ref "U10") (pin "37") (pinfunction "D+/RG2_37") (pintype "passive"))
    )
    (net (code "8") (name "/D-") (class "Default")
      (node (ref "D6") (pin "3") (pinfunction "3_3") (pintype "passive"))
      (node (ref "J2") (pin "2") (pinfunction "2_2") (pintype "passive"))
      (node (ref "J4") (pin "3") (pinfunction "3_3") (pintype "passive"))
      (node (ref "U10") (pin "36") (pinfunction "D-/RG3_36") (pintype "passive"))
    )
    (net (code "9") (name "/FB") (class "Default")
      (node (ref "C3") (pin "1") (pinfunction "1_1") (pintype "passive"))
      (node (ref "R6") (pin "1") (pinfunction "1_1") (pintype "passive"))
      (node (ref "U10") (pin "17") (pinfunction "PGEC1/AN6/RPI38/RB6_17") (pintype "passive"))
    )
    (net (code "10") (name "/GREEN") (class "Default")
      (node (ref "D2") (pin "2") (pinfunction "A_2") (pintype "passive"))
      (node (ref "U10") (pin "47") (pinfunction "PGED2/SOSCI/C3IN3-/RPI61/RC13_47") (pintype "passive"))
    )
    (net (code "11") (name "/LDO3.3V-5.0V") (class "Default")
      (node (ref "C1") (pin "1") (pinfunction "1_1") (pintype "passive"))
      (node (ref "R14") (pin "1") (pinfunction "1_1") (pintype "passive"))
      (node (ref "U29") (pin "5") (pinfunction "CTL_5") (pintype "passive"))
      (node (ref "U29") (pin "8") (pinfunction "VCC_8") (pintype "passive"))
      (node (ref "U9") (pin "5") (pinfunction "CTL_5") (pintype "passive"))
      (node (ref "U9") (pin "8") (pinfunction "VCC_8") (pintype "passive"))
    )
    (net (code "12") (name "/LDO5.0V") (class "Default")
      (node (ref "C15") (pin "1") (pinfunction "1_1") (pintype "passive"))
      (node (ref "R33") (pin "1") (pinfunction "1_1") (pintype "passive"))
      (node (ref "R34") (pin "1") (pinfunction "1_1") (pintype "passive"))
      (node (ref "U6") (pin "5") (pinfunction "CTL_5") (pintype "passive"))
      (node (ref "U6") (pin "8") (pinfunction "VCC_8") (pintype "passive"))
    )
    (net (code "13") (name "/LM12V") (class "Default")
      (node (ref "C592") (pin "1") (pinfunction "1_1") (pintype "passive"))
      (node (ref "D8") (pin "1") (pinfunction "C_1") (pintype "passive"))
      (node (ref "R13") (pin "1") (pinfunction "1_1") (pintype "passive"))
      (node (ref "U7") (pin "1") (pinfunction "Vin_1") (pintype "passive"))
    )
    (net (code "14") (name "/MCLR") (class "Default")
      (node (ref "C5") (pin "1") (pinfunction "1_1") (pintype "passive"))
      (node (ref "J1") (pin "1") (pinfunction "1_1") (pintype "passive"))
      (node (ref "R31") (pin "1") (pinfunction "1_1") (pintype "passive"))
      (node (ref "U10") (pin "7") (pinfunction "~{MCLR}_7") (pintype "passive"))
    )
    (net (code "15") (name "/MCU5.0V") (class "Default")
      (node (ref "R32") (pin "2") (pinfunction "2_2") (pintype "passive"))
      (node (ref "U10") (pin "34") (pinfunction "VBUS_34") (pintype "passive"))
    )
    (net (code "16") (name "/Main OSC In") (class "Default")
      (node (ref "C10") (pin "1") (pinfunction "1_1") (pintype "passive"))
      (node (ref "U10") (pin "39") (pinfunction "OSC1/RPI60/RC12_39") (pintype "passive"))
      (node (ref "Y1") (pin "1") (pinfunction "1_1") (pintype "passive"))
    )
    (net (code "17") (name "/Main OSC Out") (class "Default")
      (node (ref "C11") (pin "1") (pinfunction "1_1") (pintype "passive"))
      (node (ref "U10") (pin "40") (pinfunction "OSC2/CLKO/RC15_40") (pintype "passive"))
      (node (ref "Y1") (pin "2") (pinfunction "2_2") (pintype "passive"))
    )
    (net (code "18") (name "/ORANGE") (class "Default")
      (node (ref "D4") (pin "2") (pinfunction "A_2") (pintype "passive"))
      (node (ref "U10") (pin "45") (pinfunction "PMCS1/RPI75/RD11_45") (pintype "passive"))
    )
    (net (code "19") (name "/PGC") (class "Default")
      (node (ref "J1") (pin "5") (pinfunction "5_5") (pintype "passive"))
      (node (ref "U10") (pin "15") (pinfunction "PGEC3/AN1/VREF-/RPI33/RB1_15") (pintype "passive"))
    )
    (net (code "20") (name "/PGD") (class "Default")
      (node (ref "J1") (pin "4") (pinfunction "4_4") (pintype "passive"))
      (node (ref "U10") (pin "16") (pinfunction "PGED3/AN0/VREF+/RPI32/RB0_16") (pintype "passive"))
    )
    (net (code "21") (name "/PWM1H") (class "Default")
      (node (ref "TP14") (pin "1") (pinfunction "1_1") (pintype "passive"))
      (node (ref "U10") (pin "61") (pinfunction "AN25/PWM1H/PMD1/RPI81/RE1_61") (pintype "passive"))
    )
    (net (code "22") (name "/PWM1L") (class "Default")
      (node (ref "U10") (pin "60") (pinfunction "AN24/PWM1L/PMD0/RP80/RE0_60") (pintype "passive"))
    )
    (net (code "23") (name "/PWM2H") (class "Default")
      (node (ref "TP3") (pin "1") (pinfunction "1_1") (pintype "passive"))
      (node (ref "U10") (pin "63") (pinfunction "AN27/PWM2H/PMD3/RPI83/RE3_63") (pintype "passive"))
    )
    (net (code "24") (name "/PWM2L") (class "Default")
      (node (ref "U10") (pin "62") (pinfunction "AN26/PWM2L/PMD2/RP82/RE2_62") (pintype "passive"))
    )
    (net (code "25") (name "/PWM3H") (class "Default")
      (node (ref "U10") (pin "1") (pinfunction "AN29/PWM3H/PMD5/RP85/RE5_1") (pintype "passive"))
    )
    (net (code "26") (name "/PWM3L") (class "Default")
      (node (ref "TP129") (pin "1") (pinfunction "1_1") (pintype "passive"))
      (node (ref "U10") (pin "64") (pinfunction "AN28/PWM3L/PMD4/RP84/RE4_64") (pintype "passive"))
    )
    (net (code "27") (name "/PWM4H") (class "Default")
      (node (ref "U10") (pin "3") (pinfunction "AN31/PWM4H/PMD7/RP87/RE7_3") (pintype "passive"))
    )
    (net (code "28") (name "/PWM4L") (class "Default")
      (node (ref "TP128") (pin "1") (pinfunction "1_1") (pintype "passive"))
      (node (ref "U10") (pin "2") (pinfunction "AN30/PWM4L/PMD6/RPI86/RE6_2") (pintype "passive"))
    )
    (net (code "29") (name "/RED") (class "Default")
      (node (ref "D1") (pin "2") (pinfunction "A_2") (pintype "passive"))
      (node (ref "U10") (pin "48") (pinfunction "PGEC2/SOSCO/C3IN1-/T1CK/RPI62/RC14_48") (pintype "passive"))
    )
    (net (code "30") (name "/RESET_ASIC") (class "Default")
      (node (ref "R26") (pin "2") (pinfunction "2_2") (pintype "passive"))
      (node (ref "U10") (pin "43") (pinfunction "ASDA1/DPLN/RPI73/RD9_43") (pintype "passive"))
    )
    (net (code "31") (name "/SPI_CS") (class "Default")
      (node (ref "U10") (pin "8") (pinfunction "C2IN1-/PMA2/RPI121/RG9_8") (pintype "passive"))
    )
    (net (code "32") (name "/SPI_MISO") (class "Default")
      (node (ref "U10") (pin "5") (pinfunction "C1IN1-/SDI2/PMA4/RPI119/RG7_5") (pintype "passive"))
    )
    (net (code "33") (name "/SPI_MOSI") (class "Default")
      (node (ref "U10") (pin "6") (pinfunction "C2IN3-/SDO2/PMA3/RP120/RG8_6") (pintype "passive"))
    )
    (net (code "34") (name "/SPI_SCK") (class "Default")
      (node (ref "U10") (pin "4") (pinfunction "C1IN3-/SCK2/PMA5/RP118/RG6_4") (pintype "passive"))
    )
    (net (code "35") (name "/THDN") (class "Default")
      (node (ref "R9") (pin "1") (pinfunction "1_1") (pintype "passive"))
      (node (ref "U10") (pin "46") (pinfunction "INT0/DMH/RP64/RD0_46") (pintype "passive"))
    )
    (net (code "36") (name "/USB5.0V") (class "Default")
      (node (ref "D6") (pin "4") (pinfunction "4_4") (pintype "passive"))
      (node (ref "D6") (pin "6") (pinfunction "6_6") (pintype "passive"))
      (node (ref "J2") (pin "1") (pinfunction "1_1") (pintype "passive"))
      (node (ref "J4") (pin "1") (pinfunction "1_1") (pintype "passive"))
      (node (ref "R32") (pin "1") (pinfunction "1_1") (pintype "passive"))
      (node (ref "R33") (pin "2") (pinfunction "2_2") (pintype "passive"))
    )
    (net (code "37") (name "/VCAP") (class "Default")
      (node (ref "C2") (pin "1") (pinfunction "1_1") (pintype "passive"))
      (node (ref "U10") (pin "56") (pinfunction "VCAP_56") (pintype "passive"))
    )
    (net (code "38") (name "/YELLOW") (class "Default")
      (node (ref "D3") (pin "2") (pinfunction "A_2") (pintype "passive"))
      (node (ref "U10") (pin "44") (pinfunction "ASCL1/PMCS2/RPI74/RD10_44") (pintype "passive"))
    )
    (net (code "39") (name "GND") (class "Default")
      (node (ref "C1") (pin "2") (pinfunction "2_2") (pintype "passive"))
      (node (ref "C10") (pin "2") (pinfunction "2_2") (pintype "passive"))
      (node (ref "C11") (pin "2") (pinfunction "2_2") (pintype "passive"))
      (node (ref "C12") (pin "2") (pinfunction "2_2") (pintype "passive"))
      (node (ref "C13") (pin "1") (pinfunction "1_1") (pintype "passive"))
      (node (ref "C14") (pin "2") (pinfunction "2_2") (pintype "passive"))
      (node (ref "C15") (pin "2") (pinfunction "2_2") (pintype "passive"))
      (node (ref "C16") (pin "2") (pinfunction "2_2") (pintype "passive"))
      (node (ref "C17") (pin "2") (pinfunction "2_2") (pintype "passive"))
      (node (ref "C2") (pin "2") (pinfunction "2_2") (pintype "passive"))
      (node (ref "C231") (pin "2") (pinfunction "2_2") (pintype "passive"))
      (node (ref "C232") (pin "2") (pinfunction "2_2") (pintype "passive"))
      (node (ref "C3") (pin "2") (pinfunction "2_2") (pintype "passive"))
      (node (ref "C347") (pin "2") (pinfunction "2_2") (pintype "passive"))
      (node (ref "C5") (pin "2") (pinfunction "2_2") (pintype "passive"))
      (node (ref "C592") (pin "2") (pinfunction "2_2") (pintype "passive"))
      (node (ref "C6") (pin "2") (pinfunction "2_2") (pintype "passive"))
      (node (ref "C608") (pin "2") (pinfunction "2_2") (pintype "passive"))
      (node (ref "C7") (pin "2") (pinfunction "2_2") (pintype "passive"))
      (node (ref "C8") (pin "2") (pinfunction "2_2") (pintype "passive"))
      (node (ref "C9") (pin "2") (pinfunction "2_2") (pintype "passive"))
      (node (ref "D1") (pin "1") (pinfunction "C_1") (pintype "passive"))
      (node (ref "D2") (pin "1") (pinfunction "C_1") (pintype "passive"))
      (node (ref "D28") (pin "2") (pinfunction "A_2") (pintype "passive"))
      (node (ref "D3") (pin "1") (pinfunction "C_1") (pintype "passive"))
      (node (ref "D4") (pin "1") (pinfunction "C_1") (pintype "passive"))
      (node (ref "D6") (pin "2") (pinfunction "2_2") (pintype "passive"))
      (node (ref "D6") (pin "5") (pinfunction "5_5") (pintype "passive"))
      (node (ref "J1") (pin "3") (pinfunction "3_3") (pintype "passive"))
      (node (ref "J13") (pin "1") (pinfunction "1_1") (pintype "passive"))
      (node (ref "J14") (pin "1") (pinfunction "1_1") (pintype "passive"))
      (node (ref "J15") (pin "1") (pinfunction "1_1") (pintype "passive"))
      (node (ref "J2") (pin "5") (pinfunction "5_5") (pintype "passive"))
      (node (ref "J2") (pin "6") (pinfunction "6_6") (pintype "passive"))
      (node (ref "J2") (pin "7") (pinfunction "7_7") (pintype "passive"))
      (node (ref "J2") (pin "8") (pinfunction "8_8") (pintype "passive"))
      (node (ref "J2") (pin "9") (pinfunction "9_9") (pintype "passive"))
      (node (ref "J22") (pin "1") (pinfunction "1_1") (pintype "passive"))
      (node (ref "J23") (pin "1") (pinfunction "1_1") (pintype "passive"))
      (node (ref "J24") (pin "1") (pinfunction "1_1") (pintype "passive"))
      (node (ref "J3") (pin "2") (pinfunction "2_2") (pintype "passive"))
      (node (ref "J4") (pin "2") (pinfunction "2_2") (pintype "passive"))
      (node (ref "J5") (pin "4") (pinfunction "4_4") (pintype "passive"))
      (node (ref "J5") (pin "5") (pinfunction "5_5") (pintype "passive"))
      (node (ref "J5") (pin "6") (pinfunction "6_6") (pintype "passive"))
      (node (ref "J6") (pin "2") (pinfunction "2_2") (pintype "passive"))
      (node (ref "J6") (pin "3") (pinfunction "3_3") (pintype "passive"))
      (node (ref "J9") (pin "1") (pinfunction "1_1") (pintype "passive"))
      (node (ref "R17") (pin "2") (pinfunction "2_2") (pintype "passive"))
      (node (ref "R28") (pin "2") (pinfunction "2_2") (pintype "passive"))
      (node (ref "U10") (pin "20") (pinfunction "AVSS_20") (pintype "passive"))
      (node (ref "U10") (pin "25") (pinfunction "VSS_25") (pintype "passive"))
      (node (ref "U10") (pin "41") (pinfunction "VSS_41") (pintype "passive"))
      (node (ref "U10") (pin "9") (pinfunction "VSS_9") (pintype "passive"))
      (node (ref "U29") (pin "6") (pinfunction "GND_6") (pintype "passive"))
      (node (ref "U29") (pin "7") (pinfunction "GND_7") (pintype "passive"))
      (node (ref "U6") (pin "6") (pinfunction "GND_6") (pintype "passive"))
      (node (ref "U6") (pin "7") (pinfunction "GND_7") (pintype "passive"))
      (node (ref "U7") (pin "4") (pinfunction "GND_4") (pintype "passive"))
      (node (ref "U9") (pin "6") (pinfunction "GND_6") (pintype "passive"))
      (node (ref "U9") (pin "7") (pinfunction "GND_7") (pintype "passive"))
    )
    (net (code "40") (name "Net-(U9-ADJ)") (class "Default")
      (node (ref "R16") (pin "2") (pinfunction "2_2") (pintype "passive"))
      (node (ref "R17") (pin "1") (pinfunction "1_1") (pintype "passive"))
      (node (ref "U9") (pin "2") (pinfunction "ADJ_2") (pintype "passive"))
    )
    (net (code "41") (name "Net-(U10-AN2{slash}C2IN2-{slash}VMIO{slash}RPI34{slash}RB2)") (class "Default")
      (node (ref "TP7") (pin "1") (pinfunction "1_1") (pintype "passive"))
      (node (ref "U10") (pin "14") (pinfunction "AN2/C2IN2-/VMIO/RPI34/RB2_14") (pintype "passive"))
    )
    (net (code "42") (name "Net-(U10-AN3{slash}C2IN1+{slash}VPIO{slash}RPI35{slash}RB3)") (class "Default")
      (node (ref "TP6") (pin "1") (pinfunction "1_1") (pintype "passive"))
      (node (ref "U10") (pin "13") (pinfunction "AN3/C2IN1+/VPIO/RPI35/RB3_13") (pintype "passive"))
    )
    (net (code "43") (name "Net-(U10-AN4{slash}C1IN2-{slash}USBOEN{slash}RPI36{slash}RB4)") (class "Default")
      (node (ref "TP5") (pin "1") (pinfunction "1_1") (pintype "passive"))
      (node (ref "U10") (pin "12") (pinfunction "AN4/C1IN2-/USBOEN/RPI36/RB4_12") (pintype "passive"))
    )
    (net (code "44") (name "Net-(U10-AN5{slash}C1IN1+{slash}VBUSON{slash}VBUSST{slash}RPI37{slash}RB5)") (class "Default")
      (node (ref "TP29") (pin "1") (pinfunction "1_1") (pintype "passive"))
      (node (ref "U10") (pin "11") (pinfunction "AN5/C1IN1+/VBUSON/VBUSST/RPI37/RB5_11") (pintype "passive"))
    )
    (net (code "45") (name "Net-(U10-AN8{slash}PMA6{slash}RPI40{slash}RB8)") (class "Default")
      (node (ref "TP10") (pin "1") (pinfunction "1_1") (pintype "passive"))
      (node (ref "U10") (pin "21") (pinfunction "AN8/PMA6/RPI40/RB8_21") (pintype "passive"))
    )
    (net (code "46") (name "Net-(U10-AN9{slash}PMA7{slash}{slash}RPI41{slash}RB9)") (class "Default")
      (node (ref "TP11") (pin "1") (pinfunction "1_1") (pintype "passive"))
      (node (ref "U10") (pin "22") (pinfunction "AN9/PMA7//RPI41/RB9_22") (pintype "passive"))
    )
    (net (code "47") (name "Net-(U10-AN14{slash}PMA1{slash}RPI46{slash}RB14)") (class "Default")
      (node (ref "TP124") (pin "1") (pinfunction "1_1") (pintype "passive"))
      (node (ref "U10") (pin "29") (pinfunction "AN14/PMA1/RPI46/RB14_29") (pintype "passive"))
    )
    (net (code "48") (name "Net-(U10-AN15{slash}PMA0{slash}RPI47{slash}RB15)") (class "Default")
      (node (ref "TP125") (pin "1") (pinfunction "1_1") (pintype "passive"))
      (node (ref "U10") (pin "30") (pinfunction "AN15/PMA0/RPI47/RB15_30") (pintype "passive"))
    )
    (net (code "49") (name "Net-(U10-C3IN1+{slash}VCMPST3{slash}RP71{slash}RD7)") (class "Default")
      (node (ref "TP18") (pin "1") (pinfunction "1_1") (pintype "passive"))
      (node (ref "U10") (pin "55") (pinfunction "C3IN1+/VCMPST3/RP71/RD7_55") (pintype "passive"))
    )
    (net (code "50") (name "Net-(U10-C3IN2-{slash}RP70{slash}RD6)") (class "Default")
      (node (ref "TP19") (pin "1") (pinfunction "1_1") (pintype "passive"))
      (node (ref "U10") (pin "54") (pinfunction "C3IN2-/RP70/RD6_54") (pintype "passive"))
    )
    (net (code "51") (name "Net-(U10-DPH{slash}RP66{slash}RD2)") (class "Default")
      (node (ref "TP22") (pin "1") (pinfunction "1_1") (pintype "passive"))
      (node (ref "U10") (pin "50") (pinfunction "DPH/RP66/RD2_50") (pintype "passive"))
    )
    (net (code "52") (name "Net-(U10-PGED1{slash}AN7{slash}RCV{slash}RPI39{slash}RB7)") (class "Default")
      (node (ref "TP26") (pin "1") (pinfunction "1_1") (pintype "passive"))
      (node (ref "U10") (pin "18") (pinfunction "PGED1/AN7/RCV/RPI39/RB7_18") (pintype "passive"))
    )
    (net (code "53") (name "Net-(U10-PMBE{slash}RP67{slash}RD3)") (class "Default")
      (node (ref "TP17") (pin "1") (pinfunction "1_1") (pintype "passive"))
      (node (ref "U10") (pin "51") (pinfunction "PMBE/RP67/RD3_51") (pintype "passive"))
    )
    (net (code "54") (name "Net-(U10-PMRD{slash}RP69{slash}RD5)") (class "Default")
      (node (ref "TP25") (pin "1") (pinfunction "1_1") (pintype "passive"))
      (node (ref "U10") (pin "53") (pinfunction "PMRD/RP69/RD5_53") (pintype "passive"))
    )
    (net (code "55") (name "Net-(U10-PMWR{slash}RP68{slash}RD4)") (class "Default")
      (node (ref "TP20") (pin "1") (pinfunction "1_1") (pintype "passive"))
      (node (ref "U10") (pin "52") (pinfunction "PMWR/RP68/RD4_52") (pintype "passive"))
    )
    (net (code "56") (name "Net-(U10-RTCC{slash}DMLN{slash}RPI72{slash}RD8)") (class "Default")
      (node (ref "TP13") (pin "1") (pinfunction "1_1") (pintype "passive"))
      (node (ref "U10") (pin "42") (pinfunction "RTCC/DMLN/RPI72/RD8_42") (pintype "passive"))
    )
    (net (code "57") (name "Net-(U10-SCL2{slash}PMA8{slash}RP101{slash}RF5)") (class "Default")
      (node (ref "TP127") (pin "1") (pinfunction "1_1") (pintype "passive"))
      (node (ref "U10") (pin "32") (pinfunction "SCL2/PMA8/RP101/RF5_32") (pintype "passive"))
    )
    (net (code "58") (name "Net-(U10-SDA2{slash}PMA9{slash}RP100{slash}RF4)") (class "Default")
      (node (ref "TP126") (pin "1") (pinfunction "1_1") (pintype "passive"))
      (node (ref "U10") (pin "31") (pinfunction "SDA2/PMA9/RP100/RF4_31") (pintype "passive"))
    )
    (net (code "59") (name "Net-(U10-TCK{slash}AN12{slash}PMA11{slash}RPI44{slash}RB12)") (class "Default")
      (node (ref "TP2") (pin "1") (pinfunction "1_1") (pintype "passive"))
      (node (ref "U10") (pin "27") (pinfunction "TCK/AN12/PMA11/RPI44/RB12_27") (pintype "passive"))
    )
    (net (code "60") (name "Net-(U10-TDI{slash}AN13{slash}PMA10{slash}RPI45{slash}RB13)") (class "Default")
      (node (ref "TP123") (pin "1") (pinfunction "1_1") (pintype "passive"))
      (node (ref "U10") (pin "28") (pinfunction "TDI/AN13/PMA10/RPI45/RB13_28") (pintype "passive"))
    )
    (net (code "61") (name "Net-(U10-TDO{slash}AN11{slash}PMA12{slash}RPI43{slash}RB11)") (class "Default")
      (node (ref "TP132") (pin "1") (pinfunction "1_1") (pintype "passive"))
      (node (ref "U10") (pin "24") (pinfunction "TDO/AN11/PMA12/RPI43/RB11_24") (pintype "passive"))
    )
    (net (code "62") (name "Net-(U10-TMS{slash}AN10{slash}CVREF{slash}PMA13{slash}RPI42{slash}RB10)") (class "Default")
      (node (ref "TP131") (pin "1") (pinfunction "1_1") (pintype "passive"))
      (node (ref "U10") (pin "23") (pinfunction "TMS/AN10/CVREF/PMA13/RPI42/RB10_23") (pintype "passive"))
    )
    (net (code "63") (name "Net-(U10-USBID{slash}RP99{slash}RF3)") (class "Default")
      (node (ref "TP21") (pin "1") (pinfunction "1_1") (pintype "passive"))
      (node (ref "U10") (pin "33") (pinfunction "USBID/RP99/RF3_33") (pintype "passive"))
    )
    (net (code "64") (name "Net-(U10-VCMPST1{slash}RP96{slash}RF0)") (class "Default")
      (node (ref "TP12") (pin "1") (pinfunction "1_1") (pintype "passive"))
      (node (ref "U10") (pin "58") (pinfunction "VCMPST1/RP96/RF0_58") (pintype "passive"))
    )
    (net (code "65") (name "Net-(U10-VCMPST2{slash}RP97{slash}RF1)") (class "Default")
      (node (ref "TP28") (pin "1") (pinfunction "1_1") (pintype "passive"))
      (node (ref "U10") (pin "59") (pinfunction "VCMPST2/RP97/RF1_59") (pintype "passive"))
    )
    (net (code "66") (name "Net-(U10-VCPCON{slash}RP65{slash}RD1)") (class "Default")
      (node (ref "TP23") (pin "1") (pinfunction "1_1") (pintype "passive"))
      (node (ref "U10") (pin "49") (pinfunction "VCPCON/RP65/RD1_49") (pintype "passive"))
    )
    (net (code "67") (name "Net-(U29-ADJ)") (class "Default")
      (node (ref "R27") (pin "2") (pinfunction "2_2") (pintype "passive"))
      (node (ref "R28") (pin "1") (pinfunction "1_1") (pintype "passive"))
      (node (ref "U29") (pin "2") (pinfunction "ADJ_2") (pintype "passive"))
    )
    (net (code "68") (name "unconnected-(J2-Pad4)") (class "Default")
      (node (ref "J2") (pin "4") (pinfunction "4_4") (pintype "passive+no_connect"))
    )
    (net (code "69") (name "unconnected-(U6-NC-Pad2)") (class "Default")
      (node (ref "U6") (pin "2") (pinfunction "NC_2") (pintype "passive+no_connect"))
    )
    (net (code "70") (name "unconnected-(U6-NC-Pad3)") (class "Default")
      (node (ref "U6") (pin "3") (pinfunction "NC_3") (pintype "passive+no_connect"))
    )
    (net (code "71") (name "unconnected-(U6-NC-Pad4)") (class "Default")
      (node (ref "U6") (pin "4") (pinfunction "NC_4") (pintype "passive+no_connect"))
    )
    (net (code "72") (name "unconnected-(U9-NC-Pad3)") (class "Default")
      (node (ref "U9") (pin "3") (pinfunction "NC_3") (pintype "passive+no_connect"))
    )
    (net (code "73") (name "unconnected-(U9-NC-Pad4)") (class "Default")
      (node (ref "U9") (pin "4") (pinfunction "NC_4") (pintype "passive+no_connect"))
    )
    (net (code "74") (name "unconnected-(U29-NC-Pad3)") (class "Default")
      (node (ref "U29") (pin "3") (pinfunction "NC_3") (pintype "passive+no_connect"))
    )
    (net (code "75") (name "unconnected-(U29-NC-Pad4)") (class "Default")
      (node (ref "U29") (pin "4") (pinfunction "NC_4") (pintype "passive+no_connect"))
    )
  )
)
